# PHY-AUDIO-HDMI-TVout.net
KiCad netlist of a schematic drawn in Altium Designer
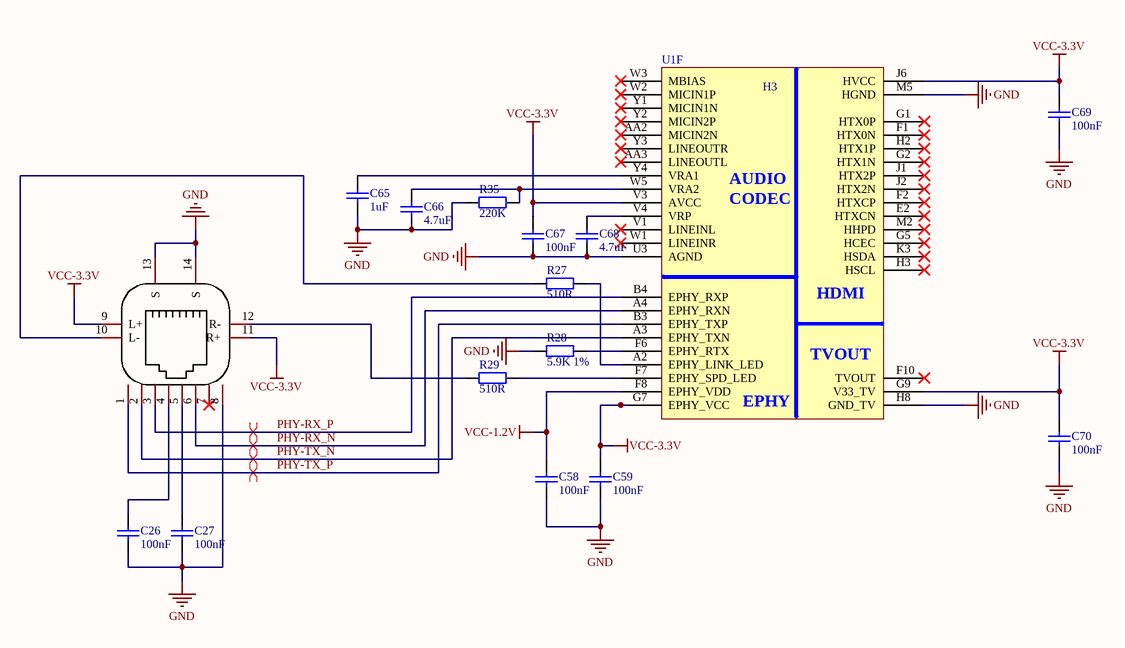
[diagram p0: PHY-AUDIO-HDMI-TVout.SchDoc]

(export (version "E")
  (design (tool "Eeschema 10.0.6"))
  (components
    (comp (ref "C26")
      (value "100nF")
      (footprint "0402_C")
      (description "smd capacitor")
      (libsource (lib "Schlib") (part "CAP-SMD"))
    )
    (comp (ref "C27")
      (value "100nF")
      (footprint "0402_C")
      (description "smd capacitor")
      (libsource (lib "Schlib") (part "CAP-SMD"))
    )
    (comp (ref "C58")
      (value "100nF")
      (footprint "0402_C")
      (description "smd capacitor")
      (libsource (lib "Schlib") (part "CAP-SMD"))
    )
    (comp (ref "C59")
      (value "100nF")
      (footprint "0402_C")
      (description "smd capacitor")
      (libsource (lib "Schlib") (part "CAP-SMD"))
    )
    (comp (ref "C65")
      (value "1uF")
      (footprint "0402_C")
      (description "smd capacitor")
      (libsource (lib "Schlib") (part "CAP-SMD"))
    )
    (comp (ref "C66")
      (value "4.7uF")
      (footprint "0402_C")
      (description "smd capacitor")
      (libsource (lib "Schlib") (part "CAP-SMD"))
    )
    (comp (ref "C67")
      (value "100nF")
      (footprint "0402_C")
      (description "smd capacitor")
      (libsource (lib "Schlib") (part "CAP-SMD"))
    )
    (comp (ref "C68")
      (value "4.7uF")
      (footprint "0402_C")
      (description "smd capacitor")
      (libsource (lib "Schlib") (part "CAP-SMD"))
    )
    (comp (ref "C69")
      (value "100nF")
      (footprint "0402_C")
      (description "smd capacitor")
      (libsource (lib "Schlib") (part "CAP-SMD"))
    )
    (comp (ref "C70")
      (value "100nF")
      (footprint "0402_C")
      (description "smd capacitor")
      (libsource (lib "Schlib") (part "CAP-SMD"))
    )
    (comp (ref "R27")
      (value "510R")
      (footprint "0402_R")
      (description "smd resistor")
      (libsource (lib "Schlib") (part "RES-SMD"))
    )
    (comp (ref "R28")
      (value "5.9K 1%")
      (footprint "0402_R")
      (description "smd resistor")
      (libsource (lib "Schlib") (part "RES-SMD"))
    )
    (comp (ref "R29")
      (value "510R")
      (footprint "0402_R")
      (description "smd resistor")
      (libsource (lib "Schlib") (part "RES-SMD"))
    )
    (comp (ref "R35")
      (value "220K")
      (footprint "0402_R")
      (description "smd resistor")
      (libsource (lib "Schlib") (part "RES-SMD"))
    )
    (comp (ref "RJ1")
      (value "R-RJ45R08P-C000")
      (footprint "R-RJ45R08P-C000")
      (description "RJ45")
      (libsource (lib "Schlib") (part "R-RJ45R08P-C000"))
    )
    (comp (ref "U1")
      (value "H3")
      (footprint "allwinner-h3")
      (description "CPU")
      (libsource (lib "Schlib") (part "H3_CPU"))
    )
  )
  (nets
    (net (code "1") (name "/PHY-RX_N") (class "Default")
      (node (ref "RJ1") (pin "6") (pinfunction "6_6") (pintype "passive"))
      (node (ref "U1") (pin "A4") (pinfunction "EPHY_RXN_A4") (pintype "passive"))
    )
    (net (code "2") (name "/PHY-RX_P") (class "Default")
      (node (ref "RJ1") (pin "3") (pinfunction "3_3") (pintype "passive"))
      (node (ref "U1") (pin "B4") (pinfunction "EPHY_RXP_B4") (pintype "passive"))
    )
    (net (code "3") (name "/PHY-TX_N") (class "Default")
      (node (ref "RJ1") (pin "2") (pinfunction "2_2") (pintype "passive"))
      (node (ref "U1") (pin "A3") (pinfunction "EPHY_TXN_A3") (pintype "passive"))
    )
    (net (code "4") (name "/PHY-TX_P") (class "Default")
      (node (ref "RJ1") (pin "1") (pinfunction "1_1") (pintype "passive"))
      (node (ref "U1") (pin "B3") (pinfunction "EPHY_TXP_B3") (pintype "passive"))
    )
    (net (code "5") (name "GND") (class "Default")
      (node (ref "C26") (pin "2") (pintype "passive"))
      (node (ref "C27") (pin "2") (pintype "passive"))
      (node (ref "C58") (pin "2") (pintype "passive"))
      (node (ref "C59") (pin "2") (pintype "passive"))
      (node (ref "C65") (pin "2") (pintype "passive"))
      (node (ref "C66") (pin "2") (pintype "passive"))
      (node (ref "C67") (pin "2") (pintype "passive"))
      (node (ref "C68") (pin "2") (pintype "passive"))
      (node (ref "C69") (pin "2") (pintype "passive"))
      (node (ref "C70") (pin "2") (pintype "passive"))
      (node (ref "R28") (pin "1") (pinfunction "1_1") (pintype "passive"))
      (node (ref "R35") (pin "1") (pinfunction "1_1") (pintype "passive"))
      (node (ref "RJ1") (pin "13") (pinfunction "S_13") (pintype "passive"))
      (node (ref "RJ1") (pin "14") (pinfunction "S_14") (pintype "passive"))
      (node (ref "RJ1") (pin "8") (pinfunction "8_8") (pintype "passive"))
      (node (ref "U1") (pin "H8") (pinfunction "GND_TV_H8") (pintype "passive"))
      (node (ref "U1") (pin "M5") (pinfunction "HGND_M5") (pintype "passive"))
      (node (ref "U1") (pin "U3") (pinfunction "AGND_U3") (pintype "passive"))
    )
    (net (code "6") (name "Net-(C26-Pad1)") (class "Default")
      (node (ref "C26") (pin "1") (pintype "passive"))
      (node (ref "RJ1") (pin "4") (pinfunction "4_4") (pintype "passive"))
    )
    (net (code "7") (name "Net-(C27-Pad1)") (class "Default")
      (node (ref "C27") (pin "1") (pintype "passive"))
      (node (ref "RJ1") (pin "5") (pinfunction "5_5") (pintype "passive"))
    )
    (net (code "8") (name "Net-(RJ1-L-)") (class "Default")
      (node (ref "R27") (pin "1") (pinfunction "1_1") (pintype "passive"))
      (node (ref "RJ1") (pin "10") (pinfunction "L-_10") (pintype "passive"))
    )
    (net (code "9") (name "Net-(RJ1-R-)") (class "Default")
      (node (ref "R29") (pin "1") (pinfunction "1_1") (pintype "passive"))
      (node (ref "RJ1") (pin "12") (pinfunction "R-_12") (pintype "passive"))
    )
    (net (code "10") (name "Net-(U1F-EPHY_LINK_LED)") (class "Default")
      (node (ref "R27") (pin "2") (pinfunction "2_2") (pintype "passive"))
      (node (ref "U1") (pin "A2") (pinfunction "EPHY_LINK_LED_A2") (pintype "passive"))
    )
    (net (code "11") (name "Net-(U1F-EPHY_RTX)") (class "Default")
      (node (ref "R28") (pin "2") (pinfunction "2_2") (pintype "passive"))
      (node (ref "U1") (pin "F6") (pinfunction "EPHY_RTX_F6") (pintype "passive"))
    )
    (net (code "12") (name "Net-(U1F-EPHY_SPD_LED)") (class "Default")
      (node (ref "R29") (pin "2") (pinfunction "2_2") (pintype "passive"))
      (node (ref "U1") (pin "F7") (pinfunction "EPHY_SPD_LED_F7") (pintype "passive"))
    )
    (net (code "13") (name "Net-(U1F-VRA1)") (class "Default")
      (node (ref "C65") (pin "1") (pintype "passive"))
      (node (ref "U1") (pin "Y4") (pinfunction "VRA1_Y4") (pintype "passive"))
    )
    (net (code "14") (name "Net-(U1F-VRA2)") (class "Default")
      (node (ref "C66") (pin "1") (pintype "passive"))
      (node (ref "R35") (pin "2") (pinfunction "2_2") (pintype "passive"))
      (node (ref "U1") (pin "W5") (pinfunction "VRA2_W5") (pintype "passive"))
    )
    (net (code "15") (name "Net-(U1F-VRP)") (class "Default")
      (node (ref "C68") (pin "1") (pintype "passive"))
      (node (ref "U1") (pin "V4") (pinfunction "VRP_V4") (pintype "passive"))
    )
    (net (code "16") (name "VCC-1.2V") (class "Default")
      (node (ref "C58") (pin "1") (pintype "passive"))
      (node (ref "U1") (pin "F8") (pinfunction "EPHY_VDD_F8") (pintype "passive"))
    )
    (net (code "17") (name "VCC-3.3V") (class "Default")
      (node (ref "C59") (pin "1") (pintype "passive"))
      (node (ref "C67") (pin "1") (pintype "passive"))
      (node (ref "C69") (pin "1") (pintype "passive"))
      (node (ref "C70") (pin "1") (pintype "passive"))
      (node (ref "RJ1") (pin "11") (pinfunction "R+_11") (pintype "passive"))
      (node (ref "RJ1") (pin "9") (pinfunction "L+_9") (pintype "passive"))
      (node (ref "U1") (pin "G7") (pinfunction "EPHY_VCC_G7") (pintype "passive"))
      (node (ref "U1") (pin "G9") (pinfunction "V33_TV_G9") (pintype "passive"))
      (node (ref "U1") (pin "J6") (pinfunction "HVCC_J6") (pintype "passive"))
      (node (ref "U1") (pin "V3") (pinfunction "AVCC_V3") (pintype "passive"))
    )
    (net (code "18") (name "unconnected-(RJ1-Pad7)") (class "Default")
      (node (ref "RJ1") (pin "7") (pinfunction "7_7") (pintype "passive+no_connect"))
    )
    (net (code "19") (name "unconnected-(U1F-HCEC-PadG5)") (class "Default")
      (node (ref "U1") (pin "G5") (pinfunction "HCEC_G5") (pintype "passive+no_connect"))
    )
    (net (code "20") (name "unconnected-(U1F-HHPD-PadM2)") (class "Default")
      (node (ref "U1") (pin "M2") (pinfunction "HHPD_M2") (pintype "passive+no_connect"))
    )
    (net (code "21") (name "unconnected-(U1F-HSCL-PadH3)") (class "Default")
      (node (ref "U1") (pin "H3") (pinfunction "HSCL_H3") (pintype "passive+no_connect"))
    )
    (net (code "22") (name "unconnected-(U1F-HSDA-PadK3)") (class "Default")
      (node (ref "U1") (pin "K3") (pinfunction "HSDA_K3") (pintype "passive+no_connect"))
    )
    (net (code "23") (name "unconnected-(U1F-HTX0N-PadF1)") (class "Default")
      (node (ref "U1") (pin "F1") (pinfunction "HTX0N_F1") (pintype "passive+no_connect"))
    )
    (net (code "24") (name "unconnected-(U1F-HTX0P-PadG1)") (class "Default")
      (node (ref "U1") (pin "G1") (pinfunction "HTX0P_G1") (pintype "passive+no_connect"))
    )
    (net (code "25") (name "unconnected-(U1F-HTX1N-PadG2)") (class "Default")
      (node (ref "U1") (pin "G2") (pinfunction "HTX1N_G2") (pintype "passive+no_connect"))
    )
    (net (code "26") (name "unconnected-(U1F-HTX1P-PadH2)") (class "Default")
      (node (ref "U1") (pin "H2") (pinfunction "HTX1P_H2") (pintype "passive+no_connect"))
    )
    (net (code "27") (name "unconnected-(U1F-HTX2N-PadJ2)") (class "Default")
      (node (ref "U1") (pin "J2") (pinfunction "HTX2N_J2") (pintype "passive+no_connect"))
    )
    (net (code "28") (name "unconnected-(U1F-HTX2P-PadJ1)") (class "Default")
      (node (ref "U1") (pin "J1") (pinfunction "HTX2P_J1") (pintype "passive+no_connect"))
    )
    (net (code "29") (name "unconnected-(U1F-HTXCN-PadE2)") (class "Default")
      (node (ref "U1") (pin "E2") (pinfunction "HTXCN_E2") (pintype "passive+no_connect"))
    )
    (net (code "30") (name "unconnected-(U1F-HTXCP-PadF2)") (class "Default")
      (node (ref "U1") (pin "F2") (pinfunction "HTXCP_F2") (pintype "passive+no_connect"))
    )
    (net (code "31") (name "unconnected-(U1F-LINEINL-PadV1)") (class "Default")
      (node (ref "U1") (pin "V1") (pinfunction "LINEINL_V1") (pintype "passive+no_connect"))
    )
    (net (code "32") (name "unconnected-(U1F-LINEINR-PadW1)") (class "Default")
      (node (ref "U1") (pin "W1") (pinfunction "LINEINR_W1") (pintype "passive+no_connect"))
    )
    (net (code "33") (name "unconnected-(U1F-LINEOUTL-PadAA3)") (class "Default")
      (node (ref "U1") (pin "AA3") (pinfunction "LINEOUTL_AA3") (pintype "passive+no_connect"))
    )
    (net (code "34") (name "unconnected-(U1F-LINEOUTR-PadY3)") (class "Default")
      (node (ref "U1") (pin "Y3") (pinfunction "LINEOUTR_Y3") (pintype "passive+no_connect"))
    )
    (net (code "35") (name "unconnected-(U1F-MBIAS-PadW3)") (class "Default")
      (node (ref "U1") (pin "W3") (pinfunction "MBIAS_W3") (pintype "passive+no_connect"))
    )
    (net (code "36") (name "unconnected-(U1F-MICIN1N-PadY1)") (class "Default")
      (node (ref "U1") (pin "Y1") (pinfunction "MICIN1N_Y1") (pintype "passive+no_connect"))
    )
    (net (code "37") (name "unconnected-(U1F-MICIN1P-PadW2)") (class "Default")
      (node (ref "U1") (pin "W2") (pinfunction "MICIN1P_W2") (pintype "passive+no_connect"))
    )
    (net (code "38") (name "unconnected-(U1F-MICIN2N-PadAA2)") (class "Default")
      (node (ref "U1") (pin "AA2") (pinfunction "MICIN2N_AA2") (pintype "passive+no_connect"))
    )
    (net (code "39") (name "unconnected-(U1F-MICIN2P-PadY2)") (class "Default")
      (node (ref "U1") (pin "Y2") (pinfunction "MICIN2P_Y2") (pintype "passive+no_connect"))
    )
    (net (code "40") (name "unconnected-(U1F-TVOUT-PadF10)") (class "Default")
      (node (ref "U1") (pin "F10") (pinfunction "TVOUT_F10") (pintype "passive+no_connect"))
    )
  )
)
